# untitled.net
KiCad netlist of a schematic drawn in EAGLE
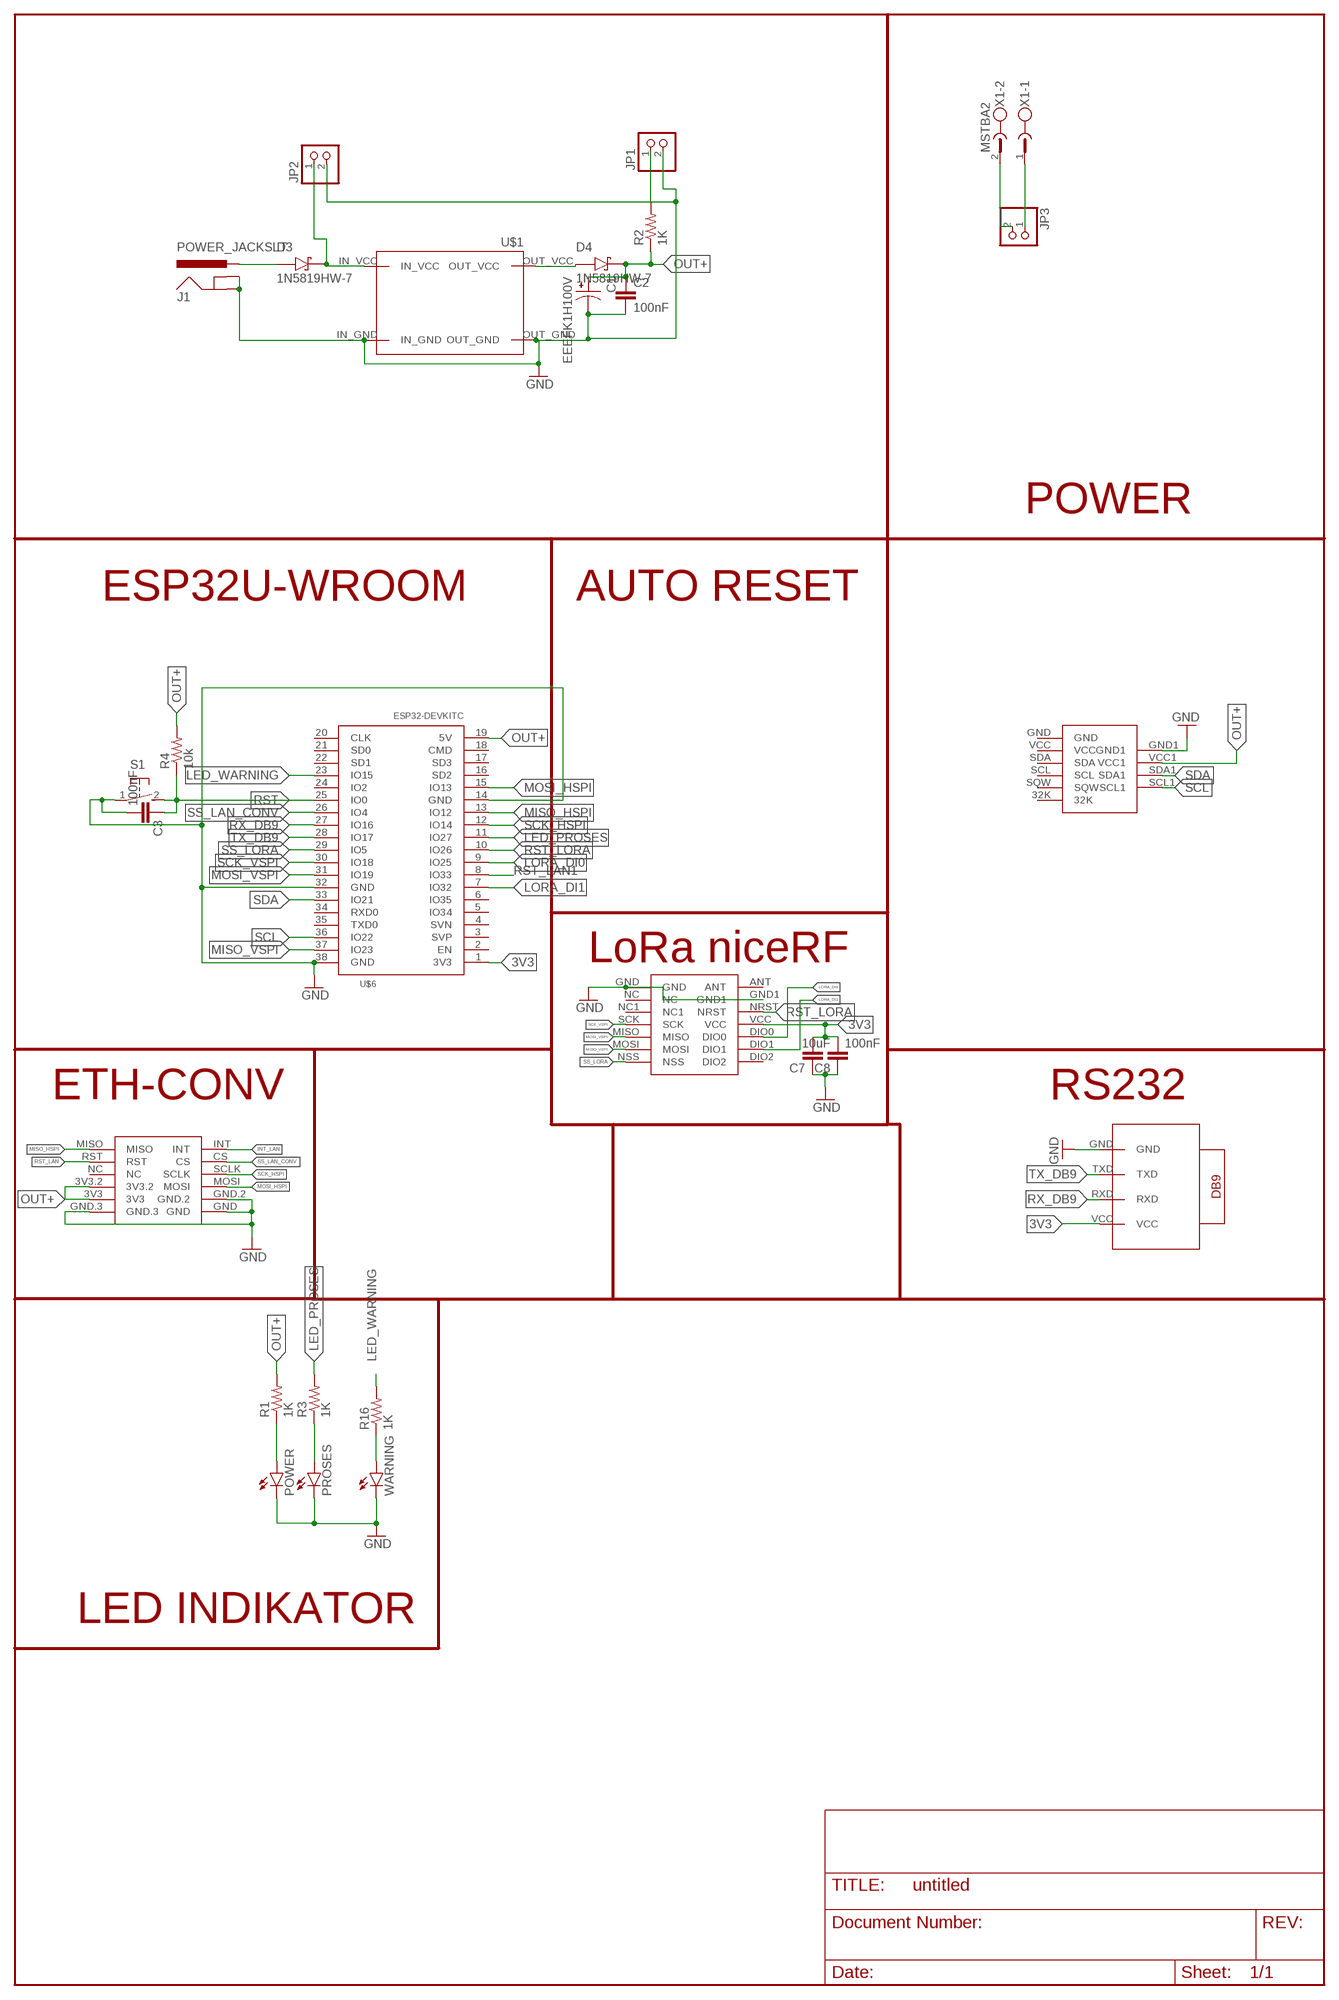
[diagram p0: schematic, sheet 1]

(export (version "E")
  (design (tool "Eeschema 10.0.6"))
  (components
    (comp (ref "C1")
      (value "EEEFK1H100V")
      (footprint "eagle-import:CAP_EEEFK1H100V")
      (fields (field (name "MF") "Panasonic"))
      (libsource (lib "eagle-import") (part "EEEFK1H100V"))
    )
    (comp (ref "C2")
      (value "100nF")
      (footprint "eagle-import:C0805K")
      (libsource (lib "eagle-import") (part "C-EUC0805K"))
    )
    (comp (ref "C3")
      (value "100nF")
      (footprint "eagle-import:C0805K")
      (libsource (lib "eagle-import") (part "C-EUC0805K"))
    )
    (comp (ref "C7")
      (value "10uF")
      (footprint "eagle-import:C0805K")
      (libsource (lib "eagle-import") (part "C-EUC0805K"))
    )
    (comp (ref "C8")
      (value "100nF")
      (footprint "eagle-import:C0805K")
      (libsource (lib "eagle-import") (part "C-EUC0805K"))
    )
    (comp (ref "D3")
      (value "1N5819HW-7")
      (footprint "eagle-import:SOD3715X145N")
      (fields (field (name "MF") "Diodes Inc."))
      (libsource (lib "eagle-import") (part "1N5819HW-7"))
    )
    (comp (ref "D4")
      (value "1N5819HW-7")
      (footprint "eagle-import:SOD3715X145N")
      (fields (field (name "MF") "Diodes Inc."))
      (libsource (lib "eagle-import") (part "1N5819HW-7"))
    )
    (comp (ref "J1")
      (value "POWER_JACKSLT")
      (footprint "eagle-import:POWER_JACK_SLOT")
      (libsource (lib "eagle-import") (part "POWER_JACKSLT"))
    )
    (comp (ref "JP1")
      (value "PINHD-1X2")
      (footprint "eagle-import:1X02")
      (libsource (lib "eagle-import") (part "PINHD-1X2"))
    )
    (comp (ref "JP2")
      (value "PINHD-1X2")
      (footprint "eagle-import:1X02")
      (libsource (lib "eagle-import") (part "PINHD-1X2"))
    )
    (comp (ref "JP3")
      (value "PINHD-1X2")
      (footprint "eagle-import:1X02")
      (libsource (lib "eagle-import") (part "PINHD-1X2"))
    )
    (comp (ref "LORA-NICERF-V1")
      (value "LORA-NICERF-V2")
      (footprint "eagle-import:LORA-NICERF-V2")
      (libsource (lib "eagle-import") (part "LORA-NICERF-V2"))
    )
    (comp (ref "POWER")
      (value "TLLR4400")
      (footprint "eagle-import:LED3MM")
      (fields (field (name "MF") "VISHAY SEMICONDUCTOR"))
      (libsource (lib "eagle-import") (part "TLLR4400"))
    )
    (comp (ref "PROSES")
      (value "TLLR4400")
      (footprint "eagle-import:LED3MM")
      (fields (field (name "MF") "VISHAY SEMICONDUCTOR"))
      (libsource (lib "eagle-import") (part "TLLR4400"))
    )
    (comp (ref "R1")
      (value "1K")
      (footprint "eagle-import:M0805")
      (libsource (lib "eagle-import") (part "R-US_M0805"))
    )
    (comp (ref "R2")
      (value "1K")
      (footprint "eagle-import:M0805")
      (libsource (lib "eagle-import") (part "R-US_M0805"))
    )
    (comp (ref "R3")
      (value "1K")
      (footprint "eagle-import:M0805")
      (libsource (lib "eagle-import") (part "R-US_M0805"))
    )
    (comp (ref "R4")
      (value "10k")
      (footprint "eagle-import:M0805")
      (libsource (lib "eagle-import") (part "R-US_M0805"))
    )
    (comp (ref "R16")
      (value "1K")
      (footprint "eagle-import:M0805")
      (libsource (lib "eagle-import") (part "R-US_M0805"))
    )
    (comp (ref "RTC1")
      (value "RTC3231")
      (footprint "eagle-import:RTC3231")
      (libsource (lib "eagle-import") (part "RTC3231"))
    )
    (comp (ref "S1")
      (value "31-XX")
      (footprint "eagle-import:B3F-31XX")
      (fields (field (name "MPN") "B3F-3100"))
      (libsource (lib "eagle-import") (part "31-XX"))
    )
    (comp (ref "U$1")
      (value "STEPDOWN_SY8205")
      (footprint "eagle-import:STEPDOWN_SY8205")
      (libsource (lib "eagle-import") (part "STEPDOWN_SY8205"))
    )
    (comp (ref "U$3")
      (value "MINI_W5500")
      (footprint "eagle-import:MINI_W5500")
      (libsource (lib "eagle-import") (part "MINI_W5500"))
    )
    (comp (ref "U$5")
      (value "RS232-BREAKOUTBREAKOUT")
      (footprint "eagle-import:RS232-BREAKOUT")
      (libsource (lib "eagle-import") (part "RS232-BREAKOUTBREAKOUT"))
    )
    (comp (ref "U$6")
      (value "ESP32DEVKITC")
      (footprint "eagle-import:ESP32-DEVKITC")
      (libsource (lib "eagle-import") (part "ESP32DEVKITC"))
    )
    (comp (ref "WARNING")
      (value "TLLR4400")
      (footprint "eagle-import:LED3MM")
      (fields (field (name "MF") "VISHAY SEMICONDUCTOR"))
      (libsource (lib "eagle-import") (part "TLLR4400"))
    )
    (comp (ref "X1")
      (value "MSTBA2")
      (footprint "eagle-import:MSTBA2")
      (fields (field (name "MF") "FARNELL") (field (name "MPN") "1757242"))
      (libsource (lib "eagle-import") (part "MSTBA2"))
    )
  )
  (nets
    (net (code "1") (name "/RST_LAN1") (class "Default")
      (node (ref "U$6") (pin "8") (pinfunction "IO33_8") (pintype "bidirectional"))
    )
    (net (code "2") (name "3V3") (class "Default")
      (node (ref "C7") (pin "2") (pinfunction "2_2") (pintype "passive"))
      (node (ref "C8") (pin "2") (pinfunction "2_2") (pintype "passive"))
      (node (ref "LORA-NICERF-V1") (pin "VCC") (pinfunction "VCC_VCC") (pintype "bidirectional"))
      (node (ref "U$5") (pin "VCC") (pinfunction "VCC_VCC") (pintype "bidirectional"))
      (node (ref "U$6") (pin "1") (pinfunction "3V3_1") (pintype "bidirectional"))
    )
    (net (code "3") (name "GND") (class "Default")
      (node (ref "C1") (pin "2") (pinfunction "2_2") (pintype "passive"))
      (node (ref "C2") (pin "2") (pinfunction "2_2") (pintype "passive"))
      (node (ref "C3") (pin "2") (pinfunction "2_2") (pintype "passive"))
      (node (ref "C7") (pin "1") (pinfunction "1_1") (pintype "passive"))
      (node (ref "C8") (pin "1") (pinfunction "1_1") (pintype "passive"))
      (node (ref "J1") (pin "GND@1") (pinfunction "GNDBREAK_GND@1") (pintype "bidirectional"))
      (node (ref "J1") (pin "GND@2") (pinfunction "GND_GND@2") (pintype "bidirectional"))
      (node (ref "JP1") (pin "2") (pinfunction "2_2") (pintype "passive"))
      (node (ref "JP2") (pin "2") (pinfunction "2_2") (pintype "passive"))
      (node (ref "LORA-NICERF-V1") (pin "GND") (pinfunction "GND_GND") (pintype "bidirectional"))
      (node (ref "LORA-NICERF-V1") (pin "GND1") (pinfunction "GND1_GND1") (pintype "bidirectional"))
      (node (ref "POWER") (pin "K") (pinfunction "C_K") (pintype "passive"))
      (node (ref "PROSES") (pin "K") (pinfunction "C_K") (pintype "passive"))
      (node (ref "RTC1") (pin "GND1") (pinfunction "GND1_GND1") (pintype "bidirectional"))
      (node (ref "S1") (pin "1") (pinfunction "P_1") (pintype "passive"))
      (node (ref "U$1") (pin "IN_GND") (pinfunction "IN_GND_IN_GND") (pintype "bidirectional"))
      (node (ref "U$1") (pin "OUT_GND") (pinfunction "OUT_GND_OUT_GND") (pintype "bidirectional"))
      (node (ref "U$3") (pin "GND") (pinfunction "GND_GND") (pintype "bidirectional"))
      (node (ref "U$3") (pin "GND.2") (pinfunction "GND.2_GND.2") (pintype "bidirectional"))
      (node (ref "U$3") (pin "GND.3") (pinfunction "GND.3_GND.3") (pintype "bidirectional"))
      (node (ref "U$5") (pin "GND") (pinfunction "GND_GND") (pintype "bidirectional"))
      (node (ref "U$6") (pin "14") (pinfunction "GND_14") (pintype "bidirectional"))
      (node (ref "U$6") (pin "32") (pinfunction "GND_32") (pintype "bidirectional"))
      (node (ref "U$6") (pin "38") (pinfunction "GND_38") (pintype "bidirectional"))
      (node (ref "WARNING") (pin "K") (pinfunction "C_K") (pintype "passive"))
    )
    (net (code "4") (name "INT_LAN") (class "Default")
      (node (ref "U$3") (pin "INT") (pinfunction "INT_INT") (pintype "bidirectional"))
    )
    (net (code "5") (name "LED_PROSES") (class "Default")
      (node (ref "R3") (pin "2") (pinfunction "2_2") (pintype "passive"))
      (node (ref "U$6") (pin "11") (pinfunction "IO27_11") (pintype "bidirectional"))
    )
    (net (code "6") (name "LED_WARNING") (class "Default")
      (node (ref "R16") (pin "2") (pinfunction "2_2") (pintype "passive"))
      (node (ref "U$6") (pin "23") (pinfunction "IO15_23") (pintype "bidirectional"))
    )
    (net (code "7") (name "LORA_DI0") (class "Default")
      (node (ref "LORA-NICERF-V1") (pin "DIO0") (pinfunction "DIO0_DIO0") (pintype "bidirectional"))
      (node (ref "U$6") (pin "9") (pinfunction "IO25_9") (pintype "bidirectional"))
    )
    (net (code "8") (name "LORA_DI1") (class "Default")
      (node (ref "LORA-NICERF-V1") (pin "DIO1") (pinfunction "DIO1_DIO1") (pintype "bidirectional"))
      (node (ref "U$6") (pin "7") (pinfunction "IO32_7") (pintype "bidirectional"))
    )
    (net (code "9") (name "MISO_HSPI") (class "Default")
      (node (ref "U$3") (pin "MISO") (pinfunction "MISO_MISO") (pintype "bidirectional"))
      (node (ref "U$6") (pin "13") (pinfunction "IO12_13") (pintype "bidirectional"))
    )
    (net (code "10") (name "MISO_VSPI") (class "Default")
      (node (ref "LORA-NICERF-V1") (pin "MOSI") (pinfunction "MOSI_MOSI") (pintype "bidirectional"))
      (node (ref "U$6") (pin "37") (pinfunction "IO23_37") (pintype "bidirectional"))
    )
    (net (code "11") (name "MOSI_HSPI") (class "Default")
      (node (ref "U$3") (pin "MOSI") (pinfunction "MOSI_MOSI") (pintype "bidirectional"))
      (node (ref "U$6") (pin "15") (pinfunction "IO13_15") (pintype "bidirectional"))
    )
    (net (code "12") (name "MOSI_VSPI") (class "Default")
      (node (ref "LORA-NICERF-V1") (pin "MISO") (pinfunction "MISO_MISO") (pintype "bidirectional"))
      (node (ref "U$6") (pin "31") (pinfunction "IO19_31") (pintype "bidirectional"))
    )
    (net (code "13") (name "Net-(D3-K)") (class "Default")
      (node (ref "D3") (pin "C") (pinfunction "K_C") (pintype "passive"))
      (node (ref "JP2") (pin "1") (pinfunction "1_1") (pintype "passive"))
      (node (ref "U$1") (pin "IN_VCC") (pinfunction "IN_VCC_IN_VCC") (pintype "bidirectional"))
    )
    (net (code "14") (name "Net-(D3-PadA)") (class "Default")
      (node (ref "D3") (pin "A") (pinfunction "A_A") (pintype "passive"))
      (node (ref "J1") (pin "PWR") (pinfunction "PWR_PWR") (pintype "bidirectional"))
    )
    (net (code "15") (name "Net-(D4-PadA)") (class "Default")
      (node (ref "D4") (pin "A") (pinfunction "A_A") (pintype "passive"))
      (node (ref "U$1") (pin "OUT_VCC") (pinfunction "OUT_VCC_OUT_VCC") (pintype "bidirectional"))
    )
    (net (code "16") (name "Net-(JP1-Pad1)") (class "Default")
      (node (ref "JP1") (pin "1") (pinfunction "1_1") (pintype "passive"))
      (node (ref "R2") (pin "2") (pinfunction "2_2") (pintype "passive"))
    )
    (net (code "17") (name "Net-(JP3-Pad1)") (class "Default")
      (node (ref "JP3") (pin "1") (pinfunction "1_1") (pintype "passive"))
      (node (ref "X1") (pin "1") (pinfunction "1_1") (pintype "passive"))
    )
    (net (code "18") (name "Net-(POWER-PadA)") (class "Default")
      (node (ref "POWER") (pin "A") (pinfunction "A_A") (pintype "passive"))
      (node (ref "R1") (pin "1") (pinfunction "1_1") (pintype "passive"))
    )
    (net (code "19") (name "Net-(PROSES-PadA)") (class "Default")
      (node (ref "PROSES") (pin "A") (pinfunction "A_A") (pintype "passive"))
      (node (ref "R3") (pin "1") (pinfunction "1_1") (pintype "passive"))
    )
    (net (code "20") (name "Net-(R16-Pad1)") (class "Default")
      (node (ref "R16") (pin "1") (pinfunction "1_1") (pintype "passive"))
      (node (ref "WARNING") (pin "A") (pinfunction "A_A") (pintype "passive"))
    )
    (net (code "21") (name "Net-(X1B-1)") (class "Default")
      (node (ref "JP3") (pin "2") (pinfunction "2_2") (pintype "passive"))
      (node (ref "X1") (pin "2") (pinfunction "1_2") (pintype "passive"))
    )
    (net (code "22") (name "OUT+") (class "Default")
      (node (ref "C1") (pin "1") (pinfunction "1_1") (pintype "passive"))
      (node (ref "C2") (pin "1") (pinfunction "1_1") (pintype "passive"))
      (node (ref "D4") (pin "C") (pinfunction "K_C") (pintype "passive"))
      (node (ref "R1") (pin "2") (pinfunction "2_2") (pintype "passive"))
      (node (ref "R2") (pin "1") (pinfunction "1_1") (pintype "passive"))
      (node (ref "R4") (pin "2") (pinfunction "2_2") (pintype "passive"))
      (node (ref "RTC1") (pin "VCC1") (pinfunction "VCC1_VCC1") (pintype "bidirectional"))
      (node (ref "U$3") (pin "3V3") (pinfunction "3V3_3V3") (pintype "bidirectional"))
      (node (ref "U$3") (pin "3V3.2") (pinfunction "3V3.2_3V3.2") (pintype "bidirectional"))
      (node (ref "U$6") (pin "19") (pinfunction "5V_19") (pintype "bidirectional"))
    )
    (net (code "23") (name "RST") (class "Default")
      (node (ref "C3") (pin "1") (pinfunction "1_1") (pintype "passive"))
      (node (ref "R4") (pin "1") (pinfunction "1_1") (pintype "passive"))
      (node (ref "S1") (pin "2") (pinfunction "S_2") (pintype "passive"))
      (node (ref "U$6") (pin "25") (pinfunction "IO0_25") (pintype "bidirectional"))
    )
    (net (code "24") (name "RST_LAN") (class "Default")
      (node (ref "U$3") (pin "RST") (pinfunction "RST_RST") (pintype "bidirectional"))
    )
    (net (code "25") (name "RST_LORA") (class "Default")
      (node (ref "LORA-NICERF-V1") (pin "NRST") (pinfunction "NRST_NRST") (pintype "bidirectional"))
      (node (ref "U$6") (pin "10") (pinfunction "IO26_10") (pintype "bidirectional"))
    )
    (net (code "26") (name "RX_DB9") (class "Default")
      (node (ref "U$5") (pin "RXD") (pinfunction "RXD_RXD") (pintype "bidirectional"))
      (node (ref "U$6") (pin "27") (pinfunction "IO16_27") (pintype "bidirectional"))
    )
    (net (code "27") (name "SCK_HSPI") (class "Default")
      (node (ref "U$3") (pin "SCLK") (pinfunction "SCLK_SCLK") (pintype "bidirectional"))
      (node (ref "U$6") (pin "12") (pinfunction "IO14_12") (pintype "bidirectional"))
    )
    (net (code "28") (name "SCK_VSPI") (class "Default")
      (node (ref "LORA-NICERF-V1") (pin "SCK") (pinfunction "SCK_SCK") (pintype "bidirectional"))
      (node (ref "U$6") (pin "30") (pinfunction "IO18_30") (pintype "bidirectional"))
    )
    (net (code "29") (name "SCL") (class "Default")
      (node (ref "RTC1") (pin "SCL1") (pinfunction "SCL1_SCL1") (pintype "bidirectional"))
      (node (ref "U$6") (pin "36") (pinfunction "IO22_36") (pintype "bidirectional"))
    )
    (net (code "30") (name "SDA") (class "Default")
      (node (ref "RTC1") (pin "SDA1") (pinfunction "SDA1_SDA1") (pintype "bidirectional"))
      (node (ref "U$6") (pin "33") (pinfunction "IO21_33") (pintype "bidirectional"))
    )
    (net (code "31") (name "SS_LAN_CONV") (class "Default")
      (node (ref "U$3") (pin "CS") (pinfunction "CS_CS") (pintype "bidirectional"))
      (node (ref "U$6") (pin "26") (pinfunction "IO4_26") (pintype "bidirectional"))
    )
    (net (code "32") (name "SS_LORA") (class "Default")
      (node (ref "LORA-NICERF-V1") (pin "NSS") (pinfunction "NSS_NSS") (pintype "bidirectional"))
      (node (ref "U$6") (pin "29") (pinfunction "IO5_29") (pintype "bidirectional"))
    )
    (net (code "33") (name "TX_DB9") (class "Default")
      (node (ref "U$5") (pin "TXD") (pinfunction "TXD_TXD") (pintype "bidirectional"))
      (node (ref "U$6") (pin "28") (pinfunction "IO17_28") (pintype "bidirectional"))
    )
    (net (code "34") (name "unconnected-(LORA-NICERF-V1-PadANT)") (class "Default")
      (node (ref "LORA-NICERF-V1") (pin "ANT") (pinfunction "ANT_ANT") (pintype "bidirectional"))
    )
    (net (code "35") (name "unconnected-(LORA-NICERF-V1-PadDIO2)") (class "Default")
      (node (ref "LORA-NICERF-V1") (pin "DIO2") (pinfunction "DIO2_DIO2") (pintype "bidirectional"))
    )
    (net (code "36") (name "unconnected-(LORA-NICERF-V1-PadNC)") (class "Default")
      (node (ref "LORA-NICERF-V1") (pin "NC") (pinfunction "NC_NC") (pintype "bidirectional"))
    )
    (net (code "37") (name "unconnected-(LORA-NICERF-V1-PadNC1)") (class "Default")
      (node (ref "LORA-NICERF-V1") (pin "NC1") (pinfunction "NC1_NC1") (pintype "bidirectional"))
    )
    (net (code "38") (name "unconnected-(RTC1-Pad32K)") (class "Default")
      (node (ref "RTC1") (pin "32K") (pinfunction "32K_32K") (pintype "bidirectional"))
    )
    (net (code "39") (name "unconnected-(RTC1-PadGND)") (class "Default")
      (node (ref "RTC1") (pin "GND") (pinfunction "GND_GND") (pintype "bidirectional"))
    )
    (net (code "40") (name "unconnected-(RTC1-PadSCL)") (class "Default")
      (node (ref "RTC1") (pin "SCL") (pinfunction "SCL_SCL") (pintype "bidirectional"))
    )
    (net (code "41") (name "unconnected-(RTC1-PadSDA)") (class "Default")
      (node (ref "RTC1") (pin "SDA") (pinfunction "SDA_SDA") (pintype "bidirectional"))
    )
    (net (code "42") (name "unconnected-(RTC1-PadSQW)") (class "Default")
      (node (ref "RTC1") (pin "SQW") (pinfunction "SQW_SQW") (pintype "bidirectional"))
    )
    (net (code "43") (name "unconnected-(RTC1-PadVCC)") (class "Default")
      (node (ref "RTC1") (pin "VCC") (pinfunction "VCC_VCC") (pintype "bidirectional"))
    )
    (net (code "44") (name "unconnected-(U$3-PadNC)") (class "Default")
      (node (ref "U$3") (pin "NC") (pinfunction "NC_NC") (pintype "bidirectional"))
    )
    (net (code "45") (name "unconnected-(U$6-CLK-Pad20)") (class "Default")
      (node (ref "U$6") (pin "20") (pinfunction "CLK_20") (pintype "bidirectional"))
    )
    (net (code "46") (name "unconnected-(U$6-CMD-Pad18)") (class "Default")
      (node (ref "U$6") (pin "18") (pinfunction "CMD_18") (pintype "bidirectional"))
    )
    (net (code "47") (name "unconnected-(U$6-EN-Pad2)") (class "Default")
      (node (ref "U$6") (pin "2") (pinfunction "EN_2") (pintype "bidirectional"))
    )
    (net (code "48") (name "unconnected-(U$6-IO2-Pad24)") (class "Default")
      (node (ref "U$6") (pin "24") (pinfunction "IO2_24") (pintype "bidirectional"))
    )
    (net (code "49") (name "unconnected-(U$6-IO34-Pad5)") (class "Default")
      (node (ref "U$6") (pin "5") (pinfunction "IO34_5") (pintype "bidirectional"))
    )
    (net (code "50") (name "unconnected-(U$6-IO35-Pad6)") (class "Default")
      (node (ref "U$6") (pin "6") (pinfunction "IO35_6") (pintype "bidirectional"))
    )
    (net (code "51") (name "unconnected-(U$6-RXD0-Pad34)") (class "Default")
      (node (ref "U$6") (pin "34") (pinfunction "RXD0_34") (pintype "bidirectional"))
    )
    (net (code "52") (name "unconnected-(U$6-SD0-Pad21)") (class "Default")
      (node (ref "U$6") (pin "21") (pinfunction "SD0_21") (pintype "bidirectional"))
    )
    (net (code "53") (name "unconnected-(U$6-SD1-Pad22)") (class "Default")
      (node (ref "U$6") (pin "22") (pinfunction "SD1_22") (pintype "bidirectional"))
    )
    (net (code "54") (name "unconnected-(U$6-SD2-Pad16)") (class "Default")
      (node (ref "U$6") (pin "16") (pinfunction "SD2_16") (pintype "bidirectional"))
    )
    (net (code "55") (name "unconnected-(U$6-SD3-Pad17)") (class "Default")
      (node (ref "U$6") (pin "17") (pinfunction "SD3_17") (pintype "bidirectional"))
    )
    (net (code "56") (name "unconnected-(U$6-SVN-Pad4)") (class "Default")
      (node (ref "U$6") (pin "4") (pinfunction "SVN_4") (pintype "bidirectional"))
    )
    (net (code "57") (name "unconnected-(U$6-SVP-Pad3)") (class "Default")
      (node (ref "U$6") (pin "3") (pinfunction "SVP_3") (pintype "bidirectional"))
    )
    (net (code "58") (name "unconnected-(U$6-TXD0-Pad35)") (class "Default")
      (node (ref "U$6") (pin "35") (pinfunction "TXD0_35") (pintype "bidirectional"))
    )
  )
)
